# NashDuino.net
KiCad netlist of a schematic drawn in EAGLE
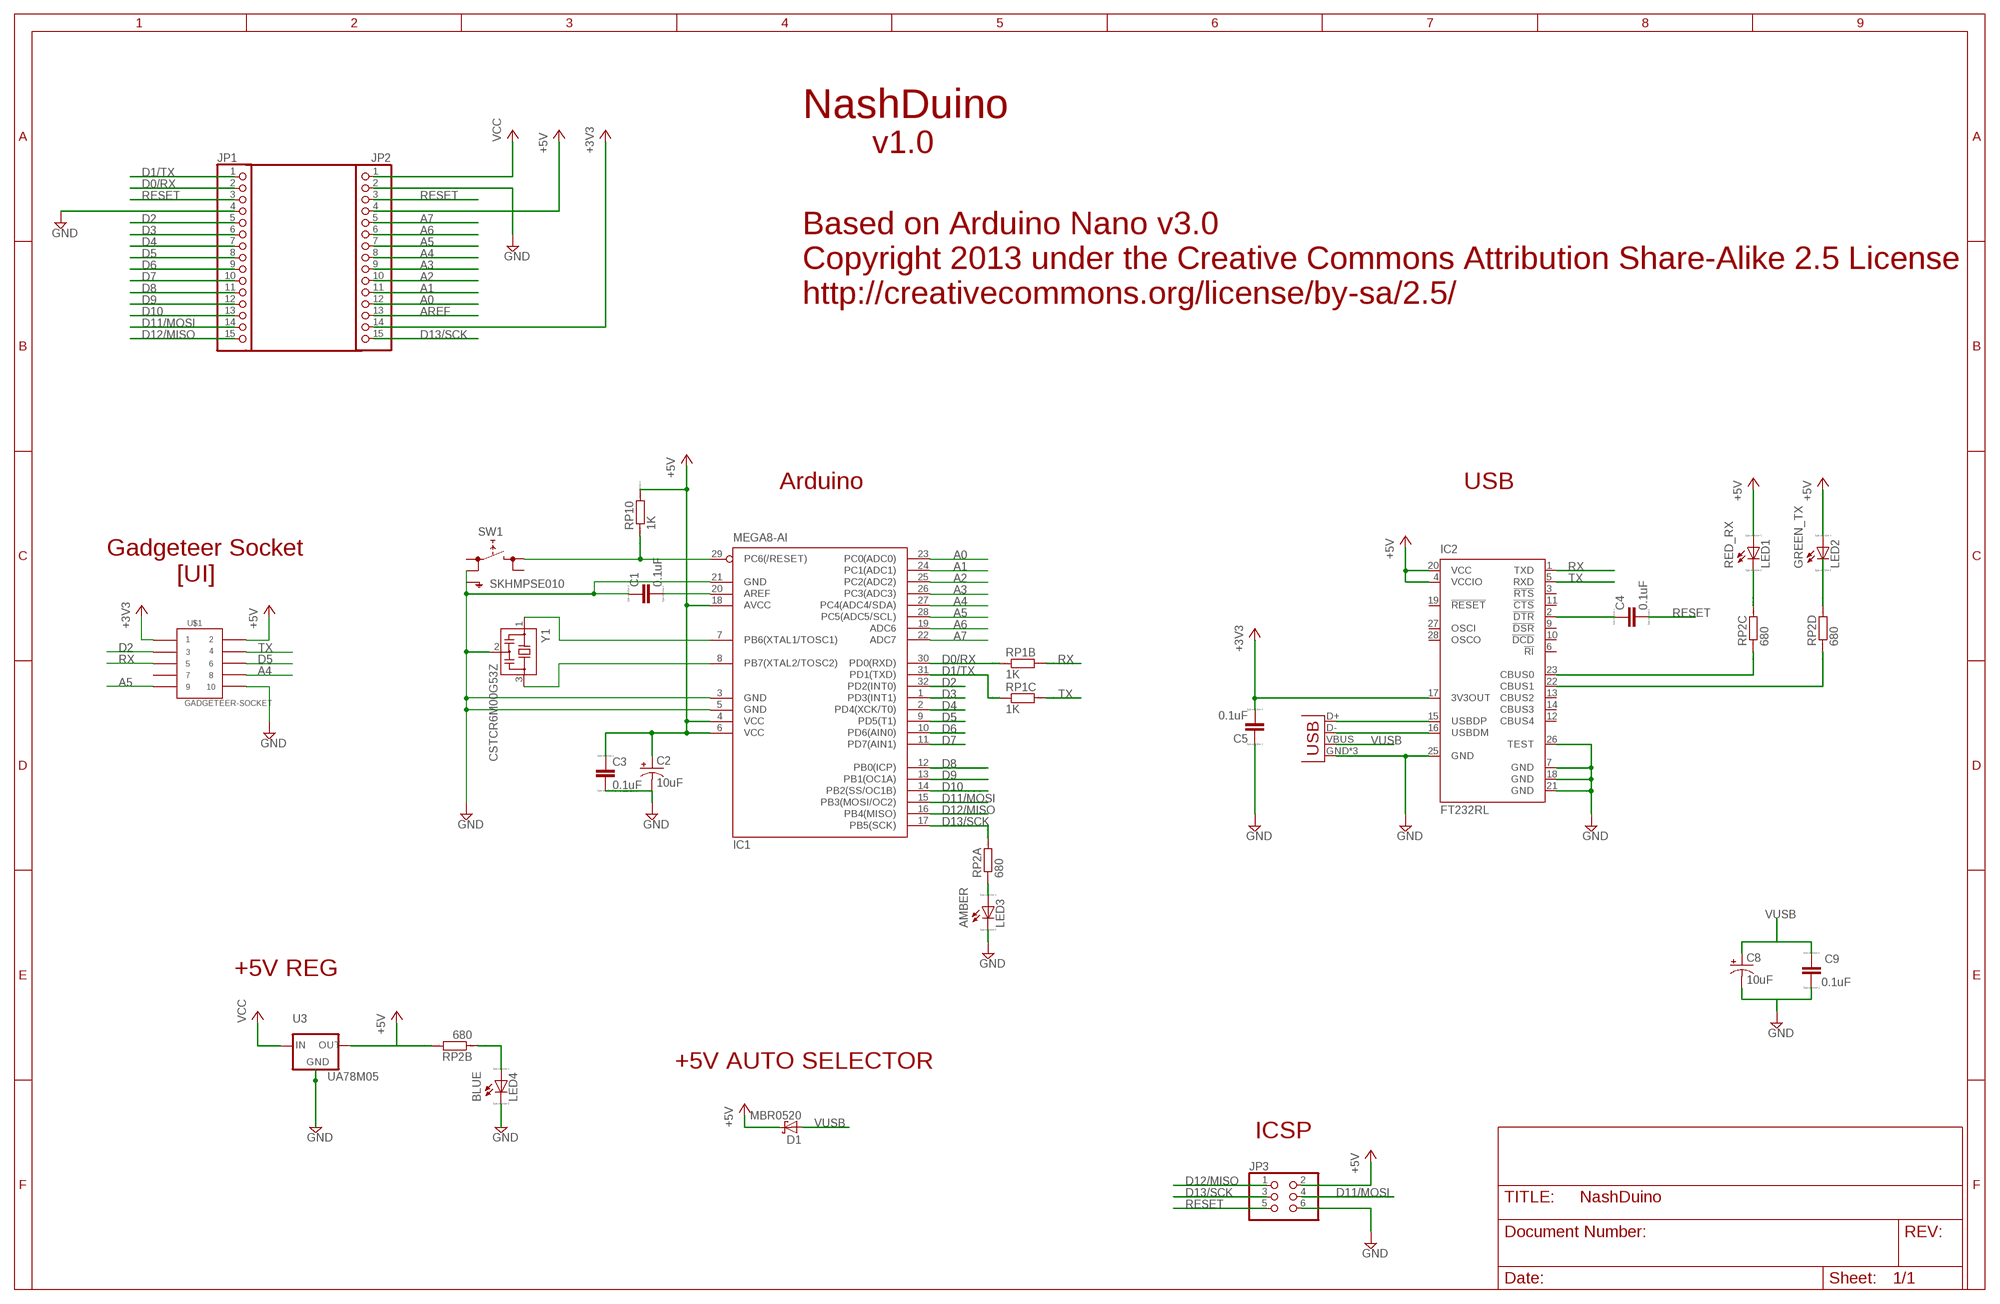
[diagram p0: schematic, sheet 1]

(export (version "E")
  (design (tool "Eeschema 10.0.6"))
  (components
    (comp (ref "C1")
      (value "0.1uF")
      (footprint "eagle-import:C1206")
      (libsource (lib "eagle-import") (part "CC1206"))
    )
    (comp (ref "C2")
      (value "10uF")
      (footprint "eagle-import:EIA3216")
      (libsource (lib "eagle-import") (part "CAP_POL1206"))
    )
    (comp (ref "C3")
      (value "0.1uF")
      (footprint "eagle-import:C0805")
      (libsource (lib "eagle-import") (part "C"))
    )
    (comp (ref "C4")
      (value "0.1uF")
      (footprint "eagle-import:C1206")
      (libsource (lib "eagle-import") (part "CC1206"))
    )
    (comp (ref "C5")
      (value "0.1uF")
      (footprint "eagle-import:C1206")
      (libsource (lib "eagle-import") (part "CC1206"))
    )
    (comp (ref "C8")
      (value "10uF")
      (footprint "eagle-import:EIA3216")
      (libsource (lib "eagle-import") (part "CAP_POL1206"))
    )
    (comp (ref "C9")
      (value "0.1uF")
      (footprint "eagle-import:C1206")
      (libsource (lib "eagle-import") (part "CC1206"))
    )
    (comp (ref "D1")
      (value "MBR0520")
      (footprint "eagle-import:SMB")
      (libsource (lib "eagle-import") (part "SCHOTTKY-DIODESMD"))
    )
    (comp (ref "IC1")
      (value "MEGA8-AI")
      (footprint "eagle-import:TQFP32-08")
      (fields (field (name "MPN") "ATMEGA8-16AU"))
      (libsource (lib "eagle-import") (part "MEGA8-AI"))
    )
    (comp (ref "IC2")
      (value "FT232RL")
      (footprint "eagle-import:SSOP28")
      (libsource (lib "eagle-import") (part "FT232RL"))
    )
    (comp (ref "JP1")
      (value "PINHD-1X15")
      (footprint "eagle-import:1X15")
      (libsource (lib "eagle-import") (part "PINHD-1X15"))
    )
    (comp (ref "JP2")
      (value "PINHD-1X15")
      (footprint "eagle-import:1X15")
      (libsource (lib "eagle-import") (part "PINHD-1X15"))
    )
    (comp (ref "JP3")
      (value "PINHD-2X3")
      (footprint "eagle-import:2X03")
      (libsource (lib "eagle-import") (part "PINHD-2X3"))
    )
    (comp (ref "JP4")
      (value "USB-MICROB")
      (footprint "eagle-import:USB-MICROB")
      (libsource (lib "eagle-import") (part "USB-MICROB"))
    )
    (comp (ref "LED1")
      (value "RED_RX")
      (footprint "eagle-import:LED_SML0603")
      (libsource (lib "eagle-import") (part "LED_ESML0603"))
    )
    (comp (ref "LED2")
      (value "GREEN_TX")
      (footprint "eagle-import:LED_SML0603")
      (libsource (lib "eagle-import") (part "LED_ESML0603"))
    )
    (comp (ref "LED3")
      (value "AMBER")
      (footprint "eagle-import:LED_SML0603")
      (libsource (lib "eagle-import") (part "LED_ESML0603"))
    )
    (comp (ref "LED4")
      (value "BLUE")
      (footprint "eagle-import:LED_SML0603")
      (libsource (lib "eagle-import") (part "LED_ESML0603"))
    )
    (comp (ref "RP1B")
      (value "1K")
      (footprint "eagle-import:R0603")
      (libsource (lib "eagle-import") (part "RR0603"))
    )
    (comp (ref "RP1C")
      (value "1K")
      (footprint "eagle-import:R0603")
      (libsource (lib "eagle-import") (part "RR0603"))
    )
    (comp (ref "RP2A")
      (value "680")
      (footprint "eagle-import:R0603")
      (libsource (lib "eagle-import") (part "RR0603"))
    )
    (comp (ref "RP2B")
      (value "680")
      (footprint "eagle-import:R0603")
      (libsource (lib "eagle-import") (part "RR0603"))
    )
    (comp (ref "RP2C")
      (value "680")
      (footprint "eagle-import:R0603")
      (libsource (lib "eagle-import") (part "RR0603"))
    )
    (comp (ref "RP2D")
      (value "680")
      (footprint "eagle-import:R0603")
      (libsource (lib "eagle-import") (part "RR0603"))
    )
    (comp (ref "RP10")
      (value "1K")
      (footprint "eagle-import:R0603")
      (libsource (lib "eagle-import") (part "RR0603"))
    )
    (comp (ref "SW1")
      (value "SKHMPSE010")
      (footprint "eagle-import:SKHMPXE010")
      (libsource (lib "eagle-import") (part "SKHMPE010S"))
    )
    (comp (ref "U$1")
      (value "GADGETEER-SOCKET")
      (footprint "eagle-import:2X5_1.27MM")
      (libsource (lib "eagle-import") (part "GADGETEER-SOCKET"))
    )
    (comp (ref "U3")
      (value "V_REG_MIC2920")
      (footprint "eagle-import:SOT223")
      (libsource (lib "eagle-import") (part "V_REG_MIC2920"))
    )
    (comp (ref "Y1")
      (value "CSTCR6M00G53Z")
      (footprint "eagle-import:CSTCR6M")
      (fields (field (name "MPN") "CSTCR6M00G53-R0"))
      (libsource (lib "eagle-import") (part "CSTCR6M00G53Z"))
    )
  )
  (nets
    (net (code "1") (name "+3V3") (class "Default")
      (node (ref "C5") (pin "2") (pinfunction "2_2") (pintype "passive"))
      (node (ref "IC2") (pin "17") (pinfunction "3V3OUT_17") (pintype "output"))
      (node (ref "JP2") (pin "14") (pinfunction "14_14") (pintype "passive"))
      (node (ref "U$1") (pin "1") (pinfunction "P$1_1") (pintype "bidirectional"))
    )
    (net (code "2") (name "+5V") (class "Default")
      (node (ref "C2") (pin "A") (pinfunction "+_A") (pintype "passive"))
      (node (ref "C3") (pin "1") (pinfunction "1_1") (pintype "passive"))
      (node (ref "D1") (pin "C") (pinfunction "C_C") (pintype "passive"))
      (node (ref "IC1") (pin "18") (pinfunction "AVCC_18") (pintype "power_in"))
      (node (ref "IC1") (pin "4") (pinfunction "VCC_4") (pintype "power_in"))
      (node (ref "IC1") (pin "6") (pinfunction "VCC_6") (pintype "power_in"))
      (node (ref "IC2") (pin "20") (pinfunction "VCC_20") (pintype "power_in"))
      (node (ref "IC2") (pin "4") (pinfunction "VCCIO_4") (pintype "power_in"))
      (node (ref "JP2") (pin "4") (pinfunction "4_4") (pintype "passive"))
      (node (ref "JP3") (pin "2") (pinfunction "2_2") (pintype "passive"))
      (node (ref "LED1") (pin "A") (pinfunction "A_A") (pintype "passive"))
      (node (ref "LED2") (pin "A") (pinfunction "A_A") (pintype "passive"))
      (node (ref "RP10") (pin "2") (pinfunction "2_2") (pintype "passive"))
      (node (ref "RP2B") (pin "2") (pinfunction "2_2") (pintype "passive"))
      (node (ref "U$1") (pin "2") (pinfunction "P$2_2") (pintype "bidirectional"))
      (node (ref "U3") (pin "3") (pinfunction "OUT_3") (pintype "output"))
    )
    (net (code "3") (name "/A0") (class "Default")
      (node (ref "IC1") (pin "23") (pinfunction "PC0(ADC0)_23") (pintype "bidirectional"))
      (node (ref "JP2") (pin "12") (pinfunction "12_12") (pintype "passive"))
    )
    (net (code "4") (name "/A1") (class "Default")
      (node (ref "IC1") (pin "24") (pinfunction "PC1(ADC1)_24") (pintype "bidirectional"))
      (node (ref "JP2") (pin "11") (pinfunction "11_11") (pintype "passive"))
    )
    (net (code "5") (name "/A2") (class "Default")
      (node (ref "IC1") (pin "25") (pinfunction "PC2(ADC2)_25") (pintype "bidirectional"))
      (node (ref "JP2") (pin "10") (pinfunction "10_10") (pintype "passive"))
    )
    (net (code "6") (name "/A3") (class "Default")
      (node (ref "IC1") (pin "26") (pinfunction "PC3(ADC3)_26") (pintype "bidirectional"))
      (node (ref "JP2") (pin "9") (pinfunction "9_9") (pintype "passive"))
    )
    (net (code "7") (name "/A4") (class "Default")
      (node (ref "IC1") (pin "27") (pinfunction "PC4(ADC4/SDA)_27") (pintype "bidirectional"))
      (node (ref "JP2") (pin "8") (pinfunction "8_8") (pintype "passive"))
      (node (ref "U$1") (pin "8") (pinfunction "P$8_8") (pintype "bidirectional"))
    )
    (net (code "8") (name "/A5") (class "Default")
      (node (ref "IC1") (pin "28") (pinfunction "PC5(ADC5/SCL)_28") (pintype "bidirectional"))
      (node (ref "JP2") (pin "7") (pinfunction "7_7") (pintype "passive"))
      (node (ref "U$1") (pin "9") (pinfunction "P$9_9") (pintype "bidirectional"))
    )
    (net (code "9") (name "/A6") (class "Default")
      (node (ref "IC1") (pin "19") (pinfunction "ADC6_19") (pintype "bidirectional"))
      (node (ref "JP2") (pin "6") (pinfunction "6_6") (pintype "passive"))
    )
    (net (code "10") (name "/A7") (class "Default")
      (node (ref "IC1") (pin "22") (pinfunction "ADC7_22") (pintype "bidirectional"))
      (node (ref "JP2") (pin "5") (pinfunction "5_5") (pintype "passive"))
    )
    (net (code "11") (name "/AREF") (class "Default")
      (node (ref "JP2") (pin "13") (pinfunction "13_13") (pintype "passive"))
    )
    (net (code "12") (name "/D0{slash}RX") (class "Default")
      (node (ref "IC1") (pin "30") (pinfunction "PD0(RXD)_30") (pintype "bidirectional"))
      (node (ref "JP1") (pin "2") (pinfunction "2_2") (pintype "passive"))
      (node (ref "RP1B") (pin "1") (pinfunction "1_1") (pintype "passive"))
    )
    (net (code "13") (name "/D1{slash}TX") (class "Default")
      (node (ref "IC1") (pin "31") (pinfunction "PD1(TXD)_31") (pintype "bidirectional"))
      (node (ref "JP1") (pin "1") (pinfunction "1_1") (pintype "passive"))
      (node (ref "RP1C") (pin "1") (pinfunction "1_1") (pintype "passive"))
    )
    (net (code "14") (name "/D2") (class "Default")
      (node (ref "IC1") (pin "32") (pinfunction "PD2(INT0)_32") (pintype "bidirectional"))
      (node (ref "JP1") (pin "5") (pinfunction "5_5") (pintype "passive"))
      (node (ref "U$1") (pin "3") (pinfunction "P$3_3") (pintype "bidirectional"))
    )
    (net (code "15") (name "/D3") (class "Default")
      (node (ref "IC1") (pin "1") (pinfunction "PD3(INT1)_1") (pintype "bidirectional"))
      (node (ref "JP1") (pin "6") (pinfunction "6_6") (pintype "passive"))
    )
    (net (code "16") (name "/D4") (class "Default")
      (node (ref "IC1") (pin "2") (pinfunction "PD4(XCK/T0)_2") (pintype "bidirectional"))
      (node (ref "JP1") (pin "7") (pinfunction "7_7") (pintype "passive"))
    )
    (net (code "17") (name "/D5") (class "Default")
      (node (ref "IC1") (pin "9") (pinfunction "PD5(T1)_9") (pintype "bidirectional"))
      (node (ref "JP1") (pin "8") (pinfunction "8_8") (pintype "passive"))
      (node (ref "U$1") (pin "6") (pinfunction "P$6_6") (pintype "bidirectional"))
    )
    (net (code "18") (name "/D6") (class "Default")
      (node (ref "IC1") (pin "10") (pinfunction "PD6(AIN0)_10") (pintype "bidirectional"))
      (node (ref "JP1") (pin "9") (pinfunction "9_9") (pintype "passive"))
    )
    (net (code "19") (name "/D7") (class "Default")
      (node (ref "IC1") (pin "11") (pinfunction "PD7(AIN1)_11") (pintype "bidirectional"))
      (node (ref "JP1") (pin "10") (pinfunction "10_10") (pintype "passive"))
    )
    (net (code "20") (name "/D8") (class "Default")
      (node (ref "IC1") (pin "12") (pinfunction "PB0(ICP)_12") (pintype "bidirectional"))
      (node (ref "JP1") (pin "11") (pinfunction "11_11") (pintype "passive"))
    )
    (net (code "21") (name "/D9") (class "Default")
      (node (ref "IC1") (pin "13") (pinfunction "PB1(OC1A)_13") (pintype "bidirectional"))
      (node (ref "JP1") (pin "12") (pinfunction "12_12") (pintype "passive"))
    )
    (net (code "22") (name "/D10") (class "Default")
      (node (ref "IC1") (pin "14") (pinfunction "PB2(SS/OC1B)_14") (pintype "bidirectional"))
      (node (ref "JP1") (pin "13") (pinfunction "13_13") (pintype "passive"))
    )
    (net (code "23") (name "/D11{slash}MOSI") (class "Default")
      (node (ref "IC1") (pin "15") (pinfunction "PB3(MOSI/OC2)_15") (pintype "bidirectional"))
      (node (ref "JP1") (pin "14") (pinfunction "14_14") (pintype "passive"))
      (node (ref "JP3") (pin "4") (pinfunction "4_4") (pintype "passive"))
    )
    (net (code "24") (name "/D12{slash}MISO") (class "Default")
      (node (ref "IC1") (pin "16") (pinfunction "PB4(MISO)_16") (pintype "bidirectional"))
      (node (ref "JP1") (pin "15") (pinfunction "15_15") (pintype "passive"))
      (node (ref "JP3") (pin "1") (pinfunction "1_1") (pintype "passive"))
    )
    (net (code "25") (name "/D13{slash}SCK") (class "Default")
      (node (ref "IC1") (pin "17") (pinfunction "PB5(SCK)_17") (pintype "bidirectional"))
      (node (ref "JP2") (pin "15") (pinfunction "15_15") (pintype "passive"))
      (node (ref "JP3") (pin "3") (pinfunction "3_3") (pintype "passive"))
      (node (ref "RP2A") (pin "2") (pinfunction "2_2") (pintype "passive"))
    )
    (net (code "26") (name "/RESET") (class "Default")
      (node (ref "C4") (pin "2") (pinfunction "2_2") (pintype "passive"))
      (node (ref "JP1") (pin "3") (pinfunction "3_3") (pintype "passive"))
      (node (ref "JP2") (pin "3") (pinfunction "3_3") (pintype "passive"))
      (node (ref "JP3") (pin "5") (pinfunction "5_5") (pintype "passive"))
    )
    (net (code "27") (name "/RX") (class "Default")
      (node (ref "IC2") (pin "1") (pinfunction "TXD_1") (pintype "output"))
      (node (ref "RP1B") (pin "2") (pinfunction "2_2") (pintype "passive"))
      (node (ref "U$1") (pin "5") (pinfunction "P$5_5") (pintype "bidirectional"))
    )
    (net (code "28") (name "/TX") (class "Default")
      (node (ref "IC2") (pin "5") (pinfunction "RXD_5") (pintype "input"))
      (node (ref "RP1C") (pin "2") (pinfunction "2_2") (pintype "passive"))
      (node (ref "U$1") (pin "4") (pinfunction "P$4_4") (pintype "bidirectional"))
    )
    (net (code "29") (name "/VUSB") (class "Default")
      (node (ref "C8") (pin "A") (pinfunction "+_A") (pintype "passive"))
      (node (ref "C9") (pin "2") (pinfunction "2_2") (pintype "passive"))
      (node (ref "D1") (pin "A") (pinfunction "A_A") (pintype "passive"))
      (node (ref "JP4") (pin "VBUS") (pinfunction "VBUS_VBUS") (pintype "bidirectional"))
    )
    (net (code "30") (name "GND") (class "Default")
      (node (ref "C1") (pin "1") (pinfunction "1_1") (pintype "passive"))
      (node (ref "C2") (pin "C") (pinfunction "-_C") (pintype "passive"))
      (node (ref "C3") (pin "2") (pinfunction "2_2") (pintype "passive"))
      (node (ref "C5") (pin "1") (pinfunction "1_1") (pintype "passive"))
      (node (ref "C8") (pin "C") (pinfunction "-_C") (pintype "passive"))
      (node (ref "C9") (pin "1") (pinfunction "1_1") (pintype "passive"))
      (node (ref "IC1") (pin "21") (pinfunction "GND_21") (pintype "power_in"))
      (node (ref "IC1") (pin "3") (pinfunction "GND_3") (pintype "power_in"))
      (node (ref "IC1") (pin "5") (pinfunction "GND_5") (pintype "power_in"))
      (node (ref "IC2") (pin "18") (pinfunction "GND_18") (pintype "power_in"))
      (node (ref "IC2") (pin "21") (pinfunction "GND_21") (pintype "power_in"))
      (node (ref "IC2") (pin "25") (pinfunction "GND_25") (pintype "power_in"))
      (node (ref "IC2") (pin "26") (pinfunction "TEST_26") (pintype "input"))
      (node (ref "IC2") (pin "7") (pinfunction "GND_7") (pintype "power_in"))
      (node (ref "JP1") (pin "4") (pinfunction "4_4") (pintype "passive"))
      (node (ref "JP2") (pin "2") (pinfunction "2_2") (pintype "passive"))
      (node (ref "JP3") (pin "6") (pinfunction "6_6") (pintype "passive"))
      (node (ref "JP4") (pin "GND") (pinfunction "GND_GND") (pintype "bidirectional"))
      (node (ref "JP4") (pin "MT1") (pinfunction "GND_MT1") (pintype "bidirectional"))
      (node (ref "JP4") (pin "MT2") (pinfunction "GND_MT2") (pintype "bidirectional"))
      (node (ref "LED3") (pin "C") (pinfunction "C_C") (pintype "passive"))
      (node (ref "SW1") (pin "2") (pinfunction "1.2_2") (pintype "passive"))
      (node (ref "SW1") (pin "5") (pinfunction "SH_5") (pintype "passive"))
      (node (ref "U$1") (pin "10") (pinfunction "P$10_10") (pintype "bidirectional"))
      (node (ref "Y1") (pin "2") (pinfunction "2_2") (pintype "passive"))
    )
    (net (code "31") (name "Net-(IC1-AREF)") (class "Default")
      (node (ref "C1") (pin "2") (pinfunction "2_2") (pintype "passive"))
      (node (ref "IC1") (pin "20") (pinfunction "AREF_20") (pintype "passive"))
    )
    (net (code "32") (name "Net-(IC1-PB6(XTAL1{slash}TOSC1))") (class "Default")
      (node (ref "IC1") (pin "7") (pinfunction "PB6(XTAL1/TOSC1)_7") (pintype "bidirectional"))
      (node (ref "Y1") (pin "1") (pinfunction "1_1") (pintype "passive"))
    )
    (net (code "33") (name "Net-(IC1-PB7(XTAL2{slash}TOSC2))") (class "Default")
      (node (ref "IC1") (pin "8") (pinfunction "PB7(XTAL2/TOSC2)_8") (pintype "bidirectional"))
      (node (ref "Y1") (pin "3") (pinfunction "3_3") (pintype "passive"))
    )
    (net (code "34") (name "Net-(IC1-PC6({slash}RESET))") (class "Default")
      (node (ref "IC1") (pin "29") (pinfunction "PC6(/RESET)_29") (pintype "bidirectional"))
      (node (ref "RP10") (pin "1") (pinfunction "1_1") (pintype "passive"))
      (node (ref "SW1") (pin "3") (pinfunction "2.1_3") (pintype "passive"))
    )
    (net (code "35") (name "Net-(IC2-CBUS0)") (class "Default")
      (node (ref "IC2") (pin "23") (pinfunction "CBUS0_23") (pintype "bidirectional"))
      (node (ref "RP2C") (pin "1") (pinfunction "1_1") (pintype "passive"))
    )
    (net (code "36") (name "Net-(IC2-CBUS1)") (class "Default")
      (node (ref "IC2") (pin "22") (pinfunction "CBUS1_22") (pintype "bidirectional"))
      (node (ref "RP2D") (pin "1") (pinfunction "1_1") (pintype "passive"))
    )
    (net (code "37") (name "Net-(IC2-USBDM)") (class "Default")
      (node (ref "IC2") (pin "16") (pinfunction "USBDM_16") (pintype "bidirectional"))
      (node (ref "JP4") (pin "D-") (pinfunction "D-_D-") (pintype "bidirectional"))
    )
    (net (code "38") (name "Net-(IC2-USBDP)") (class "Default")
      (node (ref "IC2") (pin "15") (pinfunction "USBDP_15") (pintype "bidirectional"))
      (node (ref "JP4") (pin "D+") (pinfunction "D+_D+") (pintype "bidirectional"))
    )
    (net (code "39") (name "Net-(IC2-~{DTR})") (class "Default")
      (node (ref "C4") (pin "1") (pinfunction "1_1") (pintype "passive"))
      (node (ref "IC2") (pin "2") (pinfunction "~{DTR}_2") (pintype "output"))
    )
    (net (code "40") (name "Net-(LED1-PadC)") (class "Default")
      (node (ref "LED1") (pin "C") (pinfunction "C_C") (pintype "passive"))
      (node (ref "RP2C") (pin "2") (pinfunction "2_2") (pintype "passive"))
    )
    (net (code "41") (name "Net-(LED3-PadA)") (class "Default")
      (node (ref "LED3") (pin "A") (pinfunction "A_A") (pintype "passive"))
      (node (ref "RP2A") (pin "1") (pinfunction "1_1") (pintype "passive"))
    )
    (net (code "42") (name "Net-(LED4-PadA)") (class "Default")
      (node (ref "LED4") (pin "A") (pinfunction "A_A") (pintype "passive"))
      (node (ref "RP2B") (pin "1") (pinfunction "1_1") (pintype "passive"))
    )
    (net (code "43") (name "VCC") (class "Default")
      (node (ref "JP2") (pin "1") (pinfunction "1_1") (pintype "passive"))
      (node (ref "U3") (pin "1") (pinfunction "IN_1") (pintype "input"))
    )
    (net (code "44") (name "unconnected-(IC2-CBUS2-Pad13)") (class "Default")
      (node (ref "IC2") (pin "13") (pinfunction "CBUS2_13") (pintype "bidirectional"))
    )
    (net (code "45") (name "unconnected-(IC2-CBUS3-Pad14)") (class "Default")
      (node (ref "IC2") (pin "14") (pinfunction "CBUS3_14") (pintype "bidirectional"))
    )
    (net (code "46") (name "unconnected-(IC2-CBUS4-Pad12)") (class "Default")
      (node (ref "IC2") (pin "12") (pinfunction "CBUS4_12") (pintype "bidirectional"))
    )
    (net (code "47") (name "unconnected-(IC2-OSCI-Pad27)") (class "Default")
      (node (ref "IC2") (pin "27") (pinfunction "OSCI_27") (pintype "input"))
    )
    (net (code "48") (name "unconnected-(IC2-OSCO-Pad28)") (class "Default")
      (node (ref "IC2") (pin "28") (pinfunction "OSCO_28") (pintype "output"))
    )
    (net (code "49") (name "unconnected-(IC2-~{CTS}-Pad11)") (class "Default")
      (node (ref "IC2") (pin "11") (pinfunction "~{CTS}_11") (pintype "input"))
    )
    (net (code "50") (name "unconnected-(IC2-~{DCD}-Pad10)") (class "Default")
      (node (ref "IC2") (pin "10") (pinfunction "~{DCD}_10") (pintype "input"))
    )
    (net (code "51") (name "unconnected-(IC2-~{DSR}-Pad9)") (class "Default")
      (node (ref "IC2") (pin "9") (pinfunction "~{DSR}_9") (pintype "input"))
    )
    (net (code "52") (name "unconnected-(IC2-~{RESET}-Pad19)") (class "Default")
      (node (ref "IC2") (pin "19") (pinfunction "~{RESET}_19") (pintype "input"))
    )
    (net (code "53") (name "unconnected-(IC2-~{RI}-Pad6)") (class "Default")
      (node (ref "IC2") (pin "6") (pinfunction "~{RI}_6") (pintype "input"))
    )
    (net (code "54") (name "unconnected-(IC2-~{RTS}-Pad3)") (class "Default")
      (node (ref "IC2") (pin "3") (pinfunction "~{RTS}_3") (pintype "output"))
    )
    (net (code "55") (name "unconnected-(LED2-PadC)") (class "Default")
      (node (ref "LED2") (pin "C") (pinfunction "C_C") (pintype "passive"))
    )
    (net (code "56") (name "unconnected-(LED4-PadC)") (class "Default")
      (node (ref "LED4") (pin "C") (pinfunction "C_C") (pintype "passive"))
    )
    (net (code "57") (name "unconnected-(RP2D-Pad2)") (class "Default")
      (node (ref "RP2D") (pin "2") (pinfunction "2_2") (pintype "passive"))
    )
    (net (code "58") (name "unconnected-(SW1-1.1-Pad1)") (class "Default")
      (node (ref "SW1") (pin "1") (pinfunction "1.1_1") (pintype "passive"))
    )
    (net (code "59") (name "unconnected-(SW1-2.2-Pad4)") (class "Default")
      (node (ref "SW1") (pin "4") (pinfunction "2.2_4") (pintype "passive"))
    )
    (net (code "60") (name "unconnected-(U$1-P$7-Pad7)") (class "Default")
      (node (ref "U$1") (pin "7") (pinfunction "P$7_7") (pintype "bidirectional"))
    )
    (net (code "61") (name "unconnected-(U3-GND-Pad2)") (class "Default")
      (node (ref "U3") (pin "2") (pinfunction "GND_2") (pintype "input"))
    )
  )
)
